# HashPower1.net
KiCad netlist of a schematic drawn in Altium Designer
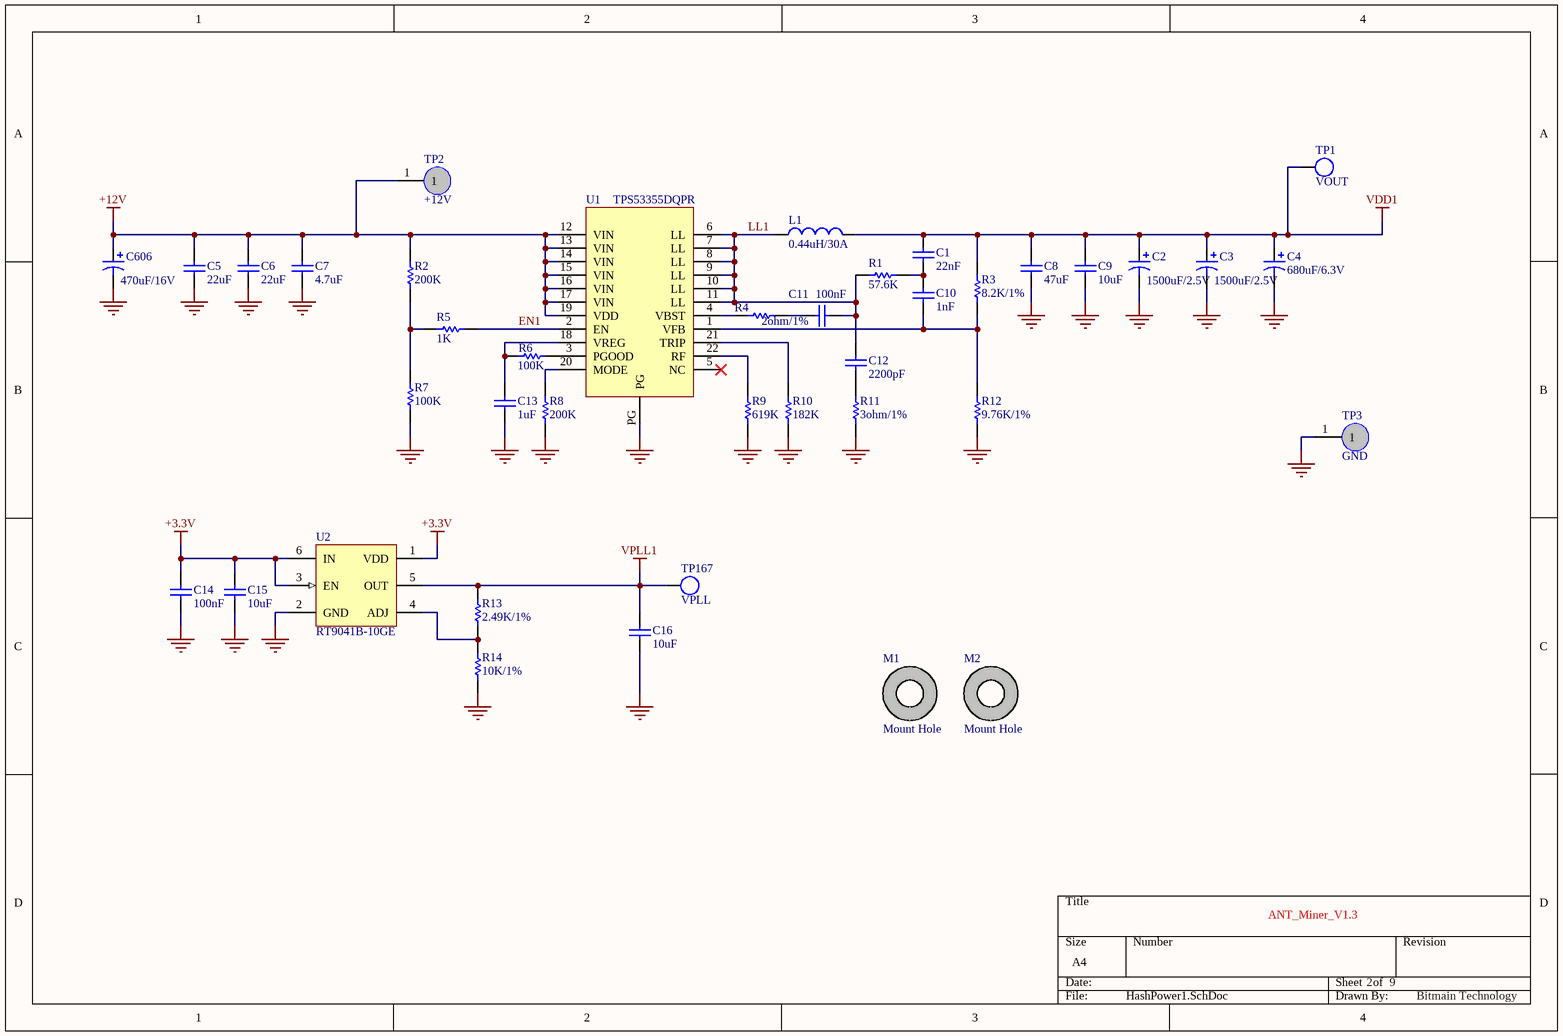
[diagram p0: HashPower1.SchDoc]

(export (version "E")
  (design (tool "Eeschema 10.0.6"))
  (components
    (comp (ref "C1")
      (value "22nF")
      (footprint "CC0603(1608)")
      (description "Capacitor")
      (libsource (lib "ANT_Miner_V1.3") (part "Cap"))
    )
    (comp (ref "C2")
      (value "1500uF/2.5V")
      (footprint "F12")
      (description "Polarized Capacitor (SMD)")
      (fields (field (name "Comment") "1500uF/4V"))
      (libsource (lib "ANT_Miner_V1.3") (part "Cap Pol2"))
    )
    (comp (ref "C3")
      (value "1500uF/2.5V")
      (footprint "F12")
      (description "Polarized Capacitor (SMD)")
      (fields (field (name "Comment") "1500uF/4V"))
      (libsource (lib "ANT_Miner_V1.3") (part "Cap Pol2"))
    )
    (comp (ref "C4")
      (value "680uF/6.3V")
      (footprint "D")
      (description "Polarized Capacitor (Surface Mount)")
      (fields (field (name "PUBLISHER") "Altium Limited"))
      (libsource (lib "Miscellaneous Devices") (part "Cap Pol3"))
    )
    (comp (ref "C5")
      (value "22uF")
      (footprint "CC1210(3225)")
      (description "Capacitor")
      (libsource (lib "ANT_Miner_V1.3") (part "Cap"))
    )
    (comp (ref "C6")
      (value "22uF")
      (footprint "CC1210(3225)")
      (description "Capacitor")
      (libsource (lib "ANT_Miner_V1.3") (part "Cap"))
    )
    (comp (ref "C7")
      (value "4.7uF")
      (footprint "CC0805(2012)")
      (description "Capacitor")
      (libsource (lib "ANT_Miner_V1.3") (part "Cap"))
    )
    (comp (ref "C8")
      (value "47uF")
      (footprint "CAPC3225L")
      (description "Capacitor (Semiconductor SIM Model)")
      (fields (field (name "PUBLISHER") "Altium Limited"))
      (libsource (lib "Miscellaneous Devices") (part "Cap Semi"))
    )
    (comp (ref "C9")
      (value "10uF")
      (footprint "CAPC2012L")
      (description "Capacitor (Semiconductor SIM Model)")
      (fields (field (name "PUBLISHER") "Altium Limited"))
      (libsource (lib "Miscellaneous Devices") (part "Cap Semi"))
    )
    (comp (ref "C10")
      (value "1nF")
      (footprint "CC0603(1608)")
      (description "Capacitor")
      (libsource (lib "ANT_Miner_V1.3") (part "Cap"))
    )
    (comp (ref "C11")
      (value "100nF")
      (footprint "CC0603(1608)")
      (description "Capacitor")
      (libsource (lib "ANT_Miner_V1.3") (part "Cap"))
    )
    (comp (ref "C12")
      (value "2200pF")
      (footprint "CC0603(1608)")
      (description "Capacitor")
      (libsource (lib "ANT_Miner_V1.3") (part "Cap"))
    )
    (comp (ref "C13")
      (value "1uF")
      (footprint "CC0603(1608)")
      (description "Capacitor")
      (libsource (lib "ANT_Miner_V1.3") (part "Cap"))
    )
    (comp (ref "C14")
      (value "100nF")
      (footprint "CC0603(1608)")
      (description "Capacitor (Semiconductor SIM Model)")
      (fields (field (name "PUBLISHER") "Altium Limited"))
      (libsource (lib "CtrlUnit_10U_V1.0") (part "Cap Semi"))
    )
    (comp (ref "C15")
      (value "10uF")
      (footprint "CC0805(2012)")
      (description "Capacitor (Semiconductor SIM Model)")
      (fields (field (name "PUBLISHER") "Altium Limited"))
      (libsource (lib "CtrlUnit_10U_V1.0") (part "Cap Semi"))
    )
    (comp (ref "C16")
      (value "10uF")
      (footprint "CC0805(2012)")
      (description "Capacitor (Semiconductor SIM Model)")
      (fields (field (name "PUBLISHER") "Altium Limited"))
      (libsource (lib "CtrlUnit_10U_V1.0") (part "Cap Semi"))
    )
    (comp (ref "C606")
      (value "470uF/16V")
      (footprint "E12")
      (description "Polarized Capacitor (SMD)")
      (libsource (lib "ANT_Miner_V1.3") (part "Cap Pol2"))
    )
    (comp (ref "L1")
      (value "0.44uH/30A")
      (footprint "IHLP5050")
      (description "Inductor")
      (fields (field (name "PUBLISHER") "Altium Limited"))
      (libsource (lib "Miscellaneous Devices") (part "Inductor"))
    )
    (comp (ref "M1") (value "Mount Hole") (footprint "HOLE_3.2") (libsource (lib "S6_2") (part "M_Hole")))
    (comp (ref "M2") (value "Mount Hole") (footprint "HOLE_3.2") (libsource (lib "S6_2") (part "M_Hole")))
    (comp (ref "R1")
      (value "57.6K")
      (footprint "RR0603(1608)")
      (description "Resistor")
      (libsource (lib "ANT_Miner_V1.3") (part "Res1"))
    )
    (comp (ref "R2")
      (value "200K")
      (footprint "RR0603(1608)")
      (description "Resistor")
      (libsource (lib "ANT_Miner_V1.3") (part "Res1"))
    )
    (comp (ref "R3")
      (value "8.2K/1%")
      (footprint "RR0603(1608)")
      (description "Resistor")
      (libsource (lib "ANT_Miner_V1.3") (part "Res1"))
    )
    (comp (ref "R4")
      (value "2ohm/1%")
      (footprint "RR0603(1608)")
      (description "Resistor")
      (fields (field (name "Comment") "2"))
      (libsource (lib "ANT_Miner_V1.3") (part "Res1"))
    )
    (comp (ref "R5")
      (value "1K")
      (footprint "RR0603(1608)")
      (description "Resistor")
      (libsource (lib "ANT_Miner_V1.3") (part "Res1"))
    )
    (comp (ref "R6")
      (value "100K")
      (footprint "RR0603(1608)")
      (description "Resistor")
      (libsource (lib "ANT_Miner_V1.3") (part "Res1"))
    )
    (comp (ref "R7")
      (value "100K")
      (footprint "RR0603(1608)")
      (description "Resistor")
      (libsource (lib "ANT_Miner_V1.3") (part "Res1"))
    )
    (comp (ref "R8")
      (value "200K")
      (footprint "RR0603(1608)")
      (description "Resistor")
      (libsource (lib "ANT_Miner_V1.3") (part "Res1"))
    )
    (comp (ref "R9")
      (value "619K")
      (footprint "RR0603(1608)")
      (description "Resistor")
      (libsource (lib "ANT_Miner_V1.3") (part "Res1"))
    )
    (comp (ref "R10")
      (value "182K")
      (footprint "RR0603(1608)")
      (description "Resistor")
      (libsource (lib "ANT_Miner_V1.3") (part "Res1"))
    )
    (comp (ref "R11")
      (value "3ohm/1%")
      (footprint "RR0603(1608)")
      (description "Resistor")
      (fields (field (name "Comment") "3"))
      (libsource (lib "ANT_Miner_V1.3") (part "Res1"))
    )
    (comp (ref "R12")
      (value "9.76K/1%")
      (footprint "RR0603(1608)")
      (description "Resistor")
      (libsource (lib "ANT_Miner_V1.3") (part "Res1"))
    )
    (comp (ref "R13")
      (value "2.49K/1%")
      (footprint "RR0603(1608)")
      (description "Resistor")
      (fields (field (name "PUBLISHER") "Altium Limited"))
      (libsource (lib "CtrlUnit_10U_V1.0") (part "Res1"))
    )
    (comp (ref "R14")
      (value "10K/1%")
      (footprint "RR0603(1608)")
      (description "Resistor")
      (fields (field (name "PUBLISHER") "Altium Limited"))
      (libsource (lib "CtrlUnit_10U_V1.0") (part "Res1"))
    )
    (comp (ref "TP1")
      (value "VOUT")
      (footprint "TP_SMD_1.0")
      (description "Test Point")
      (libsource (lib "BitMain_Miner_1") (part "TP"))
    )
    (comp (ref "TP2") (value "+12V") (footprint "TP") (libsource (lib "ANT_Miner_V1.3") (part "TP")))
    (comp (ref "TP3") (value "GND") (footprint "TP") (libsource (lib "ANT_Miner_V1.3") (part "TP")))
    (comp (ref "TP167")
      (value "VPLL")
      (footprint "TP_SMD_1.0")
      (description "Test Point")
      (libsource (lib "BitMain_Miner_1") (part "TP"))
    )
    (comp (ref "U1")
      (value "TPS53355DQPR")
      (footprint "TPS53355")
      (description "TI DC-DC,Output 30A.")
      (libsource (lib "ANT_Miner_V1.3") (part "TPS53355"))
    )
    (comp (ref "U2")
      (value "RT9041B-10GE")
      (footprint "SOT23-6_L")
      (libsource (lib "USB_Miner") (part "RT9041B-10GE"))
    )
  )
  (nets
    (net (code "1") (name "+3.3V") (class "Default")
      (node (ref "C14") (pin "2") (pinfunction "2_2") (pintype "passive"))
      (node (ref "C15") (pin "2") (pinfunction "2_2") (pintype "passive"))
      (node (ref "U2") (pin "1") (pinfunction "VDD_1") (pintype "power_in"))
      (node (ref "U2") (pin "3") (pinfunction "EN_3") (pintype "input"))
      (node (ref "U2") (pin "6") (pinfunction "IN_6") (pintype "power_in"))
    )
    (net (code "2") (name "+12V") (class "Default")
      (node (ref "C5") (pin "1") (pinfunction "1_1") (pintype "passive"))
      (node (ref "C6") (pin "1") (pinfunction "1_1") (pintype "passive"))
      (node (ref "C606") (pin "1") (pinfunction "1_1") (pintype "passive"))
      (node (ref "C7") (pin "1") (pinfunction "1_1") (pintype "passive"))
      (node (ref "R2") (pin "1") (pinfunction "1_1") (pintype "passive"))
      (node (ref "TP2") (pin "1") (pinfunction "1_1") (pintype "passive"))
      (node (ref "U1") (pin "12") (pinfunction "VIN_12") (pintype "passive"))
      (node (ref "U1") (pin "13") (pinfunction "VIN_13") (pintype "passive"))
      (node (ref "U1") (pin "14") (pinfunction "VIN_14") (pintype "passive"))
      (node (ref "U1") (pin "15") (pinfunction "VIN_15") (pintype "passive"))
      (node (ref "U1") (pin "16") (pinfunction "VIN_16") (pintype "passive"))
      (node (ref "U1") (pin "17") (pinfunction "VIN_17") (pintype "passive"))
      (node (ref "U1") (pin "19") (pinfunction "VDD_19") (pintype "passive"))
    )
    (net (code "3") (name "/EN1") (class "Default")
      (node (ref "R5") (pin "2") (pinfunction "2_2") (pintype "passive"))
      (node (ref "U1") (pin "2") (pinfunction "EN_2") (pintype "passive"))
    )
    (net (code "4") (name "/LL1") (class "Default")
      (node (ref "C11") (pin "2") (pinfunction "2_2") (pintype "passive"))
      (node (ref "C12") (pin "1") (pinfunction "1_1") (pintype "passive"))
      (node (ref "L1") (pin "1") (pinfunction "1_1") (pintype "passive"))
      (node (ref "R1") (pin "1") (pinfunction "1_1") (pintype "passive"))
      (node (ref "U1") (pin "10") (pinfunction "LL_10") (pintype "passive"))
      (node (ref "U1") (pin "11") (pinfunction "LL_11") (pintype "passive"))
      (node (ref "U1") (pin "6") (pinfunction "LL_6") (pintype "passive"))
      (node (ref "U1") (pin "7") (pinfunction "LL_7") (pintype "passive"))
      (node (ref "U1") (pin "8") (pinfunction "LL_8") (pintype "passive"))
      (node (ref "U1") (pin "9") (pinfunction "LL_9") (pintype "passive"))
    )
    (net (code "5") (name "GND") (class "Default")
      (node (ref "C13") (pin "2") (pinfunction "2_2") (pintype "passive"))
      (node (ref "C14") (pin "1") (pinfunction "1_1") (pintype "passive"))
      (node (ref "C15") (pin "1") (pinfunction "1_1") (pintype "passive"))
      (node (ref "C16") (pin "1") (pinfunction "1_1") (pintype "passive"))
      (node (ref "C2") (pin "2") (pinfunction "2_2") (pintype "passive"))
      (node (ref "C3") (pin "2") (pinfunction "2_2") (pintype "passive"))
      (node (ref "C4") (pin "2") (pinfunction "2_2") (pintype "passive"))
      (node (ref "C5") (pin "2") (pinfunction "2_2") (pintype "passive"))
      (node (ref "C6") (pin "2") (pinfunction "2_2") (pintype "passive"))
      (node (ref "C606") (pin "2") (pinfunction "2_2") (pintype "passive"))
      (node (ref "C7") (pin "2") (pinfunction "2_2") (pintype "passive"))
      (node (ref "C8") (pin "1") (pinfunction "1_1") (pintype "passive"))
      (node (ref "C9") (pin "1") (pinfunction "1_1") (pintype "passive"))
      (node (ref "R10") (pin "2") (pinfunction "2_2") (pintype "passive"))
      (node (ref "R11") (pin "2") (pinfunction "2_2") (pintype "passive"))
      (node (ref "R12") (pin "2") (pinfunction "2_2") (pintype "passive"))
      (node (ref "R14") (pin "1") (pinfunction "1_1") (pintype "passive"))
      (node (ref "R7") (pin "2") (pinfunction "2_2") (pintype "passive"))
      (node (ref "R8") (pin "2") (pinfunction "2_2") (pintype "passive"))
      (node (ref "R9") (pin "2") (pinfunction "2_2") (pintype "passive"))
      (node (ref "TP3") (pin "1") (pinfunction "1_1") (pintype "passive"))
      (node (ref "U1") (pin "PG") (pinfunction "PG_PG") (pintype "passive"))
      (node (ref "U2") (pin "2") (pinfunction "GND_2") (pintype "power_in"))
    )
    (net (code "6") (name "Net-(C1-Pad2)") (class "Default")
      (node (ref "C1") (pin "2") (pinfunction "2_2") (pintype "passive"))
      (node (ref "C10") (pin "1") (pinfunction "1_1") (pintype "passive"))
      (node (ref "R1") (pin "2") (pinfunction "2_2") (pintype "passive"))
    )
    (net (code "7") (name "Net-(C11-Pad1)") (class "Default")
      (node (ref "C11") (pin "1") (pinfunction "1_1") (pintype "passive"))
      (node (ref "R4") (pin "2") (pinfunction "2_2") (pintype "passive"))
    )
    (net (code "8") (name "Net-(C12-Pad2)") (class "Default")
      (node (ref "C12") (pin "2") (pinfunction "2_2") (pintype "passive"))
      (node (ref "R11") (pin "1") (pinfunction "1_1") (pintype "passive"))
    )
    (net (code "9") (name "Net-(R2-Pad2)") (class "Default")
      (node (ref "R2") (pin "2") (pinfunction "2_2") (pintype "passive"))
      (node (ref "R5") (pin "1") (pinfunction "1_1") (pintype "passive"))
      (node (ref "R7") (pin "1") (pinfunction "1_1") (pintype "passive"))
    )
    (net (code "10") (name "Net-(U1-MODE)") (class "Default")
      (node (ref "R8") (pin "1") (pinfunction "1_1") (pintype "passive"))
      (node (ref "U1") (pin "20") (pinfunction "MODE_20") (pintype "passive"))
    )
    (net (code "11") (name "Net-(U1-PGOOD)") (class "Default")
      (node (ref "R6") (pin "2") (pinfunction "2_2") (pintype "passive"))
      (node (ref "U1") (pin "3") (pinfunction "PGOOD_3") (pintype "passive"))
    )
    (net (code "12") (name "Net-(U1-RF)") (class "Default")
      (node (ref "R9") (pin "1") (pinfunction "1_1") (pintype "passive"))
      (node (ref "U1") (pin "22") (pinfunction "RF_22") (pintype "passive"))
    )
    (net (code "13") (name "Net-(U1-TRIP)") (class "Default")
      (node (ref "R10") (pin "1") (pinfunction "1_1") (pintype "passive"))
      (node (ref "U1") (pin "21") (pinfunction "TRIP_21") (pintype "passive"))
    )
    (net (code "14") (name "Net-(U1-VBST)") (class "Default")
      (node (ref "R4") (pin "1") (pinfunction "1_1") (pintype "passive"))
      (node (ref "U1") (pin "4") (pinfunction "VBST_4") (pintype "passive"))
    )
    (net (code "15") (name "Net-(U1-VFB)") (class "Default")
      (node (ref "C10") (pin "2") (pinfunction "2_2") (pintype "passive"))
      (node (ref "R12") (pin "1") (pinfunction "1_1") (pintype "passive"))
      (node (ref "R3") (pin "2") (pinfunction "2_2") (pintype "passive"))
      (node (ref "U1") (pin "1") (pinfunction "VFB_1") (pintype "passive"))
    )
    (net (code "16") (name "Net-(U1-VREG)") (class "Default")
      (node (ref "C13") (pin "1") (pinfunction "1_1") (pintype "passive"))
      (node (ref "R6") (pin "1") (pinfunction "1_1") (pintype "passive"))
      (node (ref "U1") (pin "18") (pinfunction "VREG_18") (pintype "passive"))
    )
    (net (code "17") (name "Net-(U2-ADJ)") (class "Default")
      (node (ref "R13") (pin "1") (pinfunction "1_1") (pintype "passive"))
      (node (ref "R14") (pin "2") (pinfunction "2_2") (pintype "passive"))
      (node (ref "U2") (pin "4") (pinfunction "ADJ_4") (pintype "passive"))
    )
    (net (code "18") (name "VDD1") (class "Default")
      (node (ref "C1") (pin "1") (pinfunction "1_1") (pintype "passive"))
      (node (ref "C2") (pin "1") (pinfunction "1_1") (pintype "passive"))
      (node (ref "C3") (pin "1") (pinfunction "1_1") (pintype "passive"))
      (node (ref "C4") (pin "1") (pinfunction "1_1") (pintype "passive"))
      (node (ref "C8") (pin "2") (pinfunction "2_2") (pintype "passive"))
      (node (ref "C9") (pin "2") (pinfunction "2_2") (pintype "passive"))
      (node (ref "L1") (pin "2") (pinfunction "2_2") (pintype "passive"))
      (node (ref "R3") (pin "1") (pinfunction "1_1") (pintype "passive"))
      (node (ref "TP1") (pin "1") (pinfunction "1_1") (pintype "passive"))
    )
    (net (code "19") (name "VPLL1") (class "Default")
      (node (ref "C16") (pin "2") (pinfunction "2_2") (pintype "passive"))
      (node (ref "R13") (pin "2") (pinfunction "2_2") (pintype "passive"))
      (node (ref "TP167") (pin "1") (pinfunction "1_1") (pintype "passive"))
      (node (ref "U2") (pin "5") (pinfunction "OUT_5") (pintype "power_in"))
    )
    (net (code "20") (name "unconnected-(M1-PIN-Pad0)") (class "Default")
      (node (ref "M1") (pin "0") (pinfunction "PIN_0") (pintype "power_in"))
    )
    (net (code "21") (name "unconnected-(M2-PIN-Pad0)") (class "Default")
      (node (ref "M2") (pin "0") (pinfunction "PIN_0") (pintype "power_in"))
    )
    (net (code "22") (name "unconnected-(U1-NC-Pad5)") (class "Default")
      (node (ref "U1") (pin "5") (pinfunction "NC_5") (pintype "passive+no_connect"))
    )
  )
)
